# CO5-AT.net
KiCad netlist of a schematic drawn in EAGLE
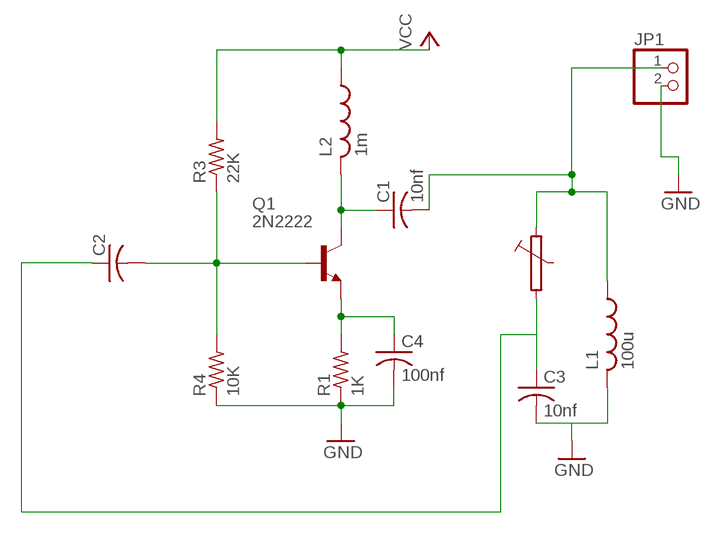
[diagram p0: schematic, sheet 1]

(export (version "E")
  (design (tool "Eeschema 10.0.6"))
  (components
    (comp (ref "C1")
      (value "10nf")
      (footprint "eagle-import:C050-025X075")
      (libsource (lib "eagle-import") (part "C-US050-025X075"))
    )
    (comp (ref "C2")
      (value "C-US050-025X075")
      (footprint "eagle-import:C050-025X075")
      (libsource (lib "eagle-import") (part "C-US050-025X075"))
    )
    (comp (ref "C3")
      (value "10nf")
      (footprint "eagle-import:C050-025X075")
      (libsource (lib "eagle-import") (part "C-US050-025X075"))
    )
    (comp (ref "C4")
      (value "100nf")
      (footprint "eagle-import:C050-025X075")
      (libsource (lib "eagle-import") (part "C-US050-025X075"))
    )
    (comp (ref "JP1")
      (value "PINHD-1X2")
      (footprint "eagle-import:1X02")
      (libsource (lib "eagle-import") (part "PINHD-1X2"))
    )
    (comp (ref "L1")
      (value "100u")
      (footprint "eagle-import:0207_10")
      (libsource (lib "eagle-import") (part "L-US0207/10"))
    )
    (comp (ref "L2")
      (value "1m")
      (footprint "eagle-import:0207_10")
      (libsource (lib "eagle-import") (part "L-US0207/10"))
    )
    (comp (ref "Q1")
      (value "2N2222")
      (footprint "eagle-import:TO18")
      (libsource (lib "eagle-import") (part "2N2222"))
    )
    (comp (ref "R1")
      (value "1K")
      (footprint "eagle-import:0207_10")
      (libsource (lib "eagle-import") (part "R-US_0207/10"))
    )
    (comp (ref "R3")
      (value "22K")
      (footprint "eagle-import:0207_10")
      (libsource (lib "eagle-import") (part "R-US_0207/10"))
    )
    (comp (ref "R4")
      (value "10K")
      (footprint "eagle-import:0207_10")
      (libsource (lib "eagle-import") (part "R-US_0207/10"))
    )
  )
  (nets
    (net (code "1") (name "GND") (class "Default")
      (node (ref "C4") (pin "2") (pinfunction "2_2") (pintype "passive"))
      (node (ref "JP1") (pin "2") (pinfunction "2_2") (pintype "passive"))
      (node (ref "R1") (pin "1") (pinfunction "1_1") (pintype "passive"))
      (node (ref "R4") (pin "1") (pinfunction "1_1") (pintype "passive"))
    )
    (net (code "2") (name "Net-(C1-Pad2)") (class "Default")
      (node (ref "C1") (pin "2") (pinfunction "2_2") (pintype "passive"))
      (node (ref "JP1") (pin "1") (pinfunction "1_1") (pintype "passive"))
      (node (ref "L1") (pin "1") (pinfunction "1_1") (pintype "passive"))
    )
    (net (code "3") (name "Net-(C3-Pad2)") (class "Default")
      (node (ref "C3") (pin "2") (pinfunction "2_2") (pintype "passive"))
      (node (ref "L1") (pin "2") (pinfunction "2_2") (pintype "passive"))
    )
    (net (code "4") (name "Net-(Q1-B)") (class "Default")
      (node (ref "C2") (pin "2") (pinfunction "2_2") (pintype "passive"))
      (node (ref "Q1") (pin "2") (pinfunction "B_2") (pintype "passive"))
      (node (ref "R3") (pin "1") (pinfunction "1_1") (pintype "passive"))
      (node (ref "R4") (pin "2") (pinfunction "2_2") (pintype "passive"))
    )
    (net (code "5") (name "Net-(Q1-C)") (class "Default")
      (node (ref "C1") (pin "1") (pinfunction "1_1") (pintype "passive"))
      (node (ref "L2") (pin "2") (pinfunction "2_2") (pintype "passive"))
      (node (ref "Q1") (pin "3") (pinfunction "C_3") (pintype "passive"))
    )
    (net (code "6") (name "Net-(Q1-E)") (class "Default")
      (node (ref "C4") (pin "1") (pinfunction "1_1") (pintype "passive"))
      (node (ref "Q1") (pin "1") (pinfunction "E_1") (pintype "passive"))
      (node (ref "R1") (pin "2") (pinfunction "2_2") (pintype "passive"))
    )
    (net (code "7") (name "VCC") (class "Default")
      (node (ref "L2") (pin "1") (pinfunction "1_1") (pintype "passive"))
      (node (ref "R3") (pin "2") (pinfunction "2_2") (pintype "passive"))
    )
    (net (code "8") (name "unconnected-(C2-Pad1)") (class "Default")
      (node (ref "C2") (pin "1") (pinfunction "1_1") (pintype "passive"))
    )
    (net (code "9") (name "unconnected-(C3-Pad1)") (class "Default")
      (node (ref "C3") (pin "1") (pinfunction "1_1") (pintype "passive"))
    )
  )
)
